# Preamp.net
KiCad netlist of a schematic drawn in Altium Designer
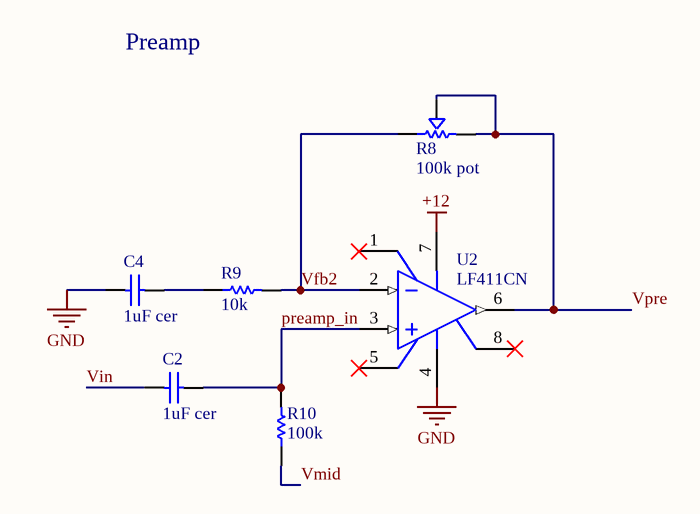
[diagram p0: Preamp.SchDoc]

(export (version "E")
  (design (tool "Eeschema 10.0.6"))
  (components
    (comp (ref "C2")
      (value "1uF cer")
      (footprint "PCB-19304320-1")
      (description "Capacitor; Ceramic; Cap 1.00uF; Tol 10%; Radial; Vol-Rtg 50V")
      (fields (field (name "MANUFACTURER PART NUMBER") "C330C105K5R5TA"))
      (libsource (lib "Octopart library") (part "SYM-bb267075e97664e1-1"))
    )
    (comp (ref "C4")
      (value "1uF cer")
      (footprint "PCB-19304320-1")
      (description "Capacitor; Ceramic; Cap 1.00uF; Tol 10%; Radial; Vol-Rtg 50V")
      (fields (field (name "MANUFACTURER PART NUMBER") "C330C105K5R5TA"))
      (libsource (lib "Octopart library") (part "SYM-bb267075e97664e1-1"))
    )
    (comp (ref "R8")
      (value "100k pot")
      (footprint "PCB-urdemwrt71ubtqm2k8m7-1")
      (description "Res Conductive Plastic POT 50K Ohm 20% 1/4W 1Turn 3.18mm Pin Panel Mount/Through Hole")
      (fields (field (name "MANUFACTURER PART NUMBER") "3310C-001-503L"))
      (libsource (lib "CommunityVault") (part "SYM-1209584-1"))
    )
    (comp (ref "R9")
      (value "10k")
      (footprint "PCB-ufx52wqpb97u1085hkka-1")
      (description "Through Hole Carbon Film Resistor, CFR Series, 10 kohm, 500 mW, - 5%, 350 V, Axial Leaded")
      (libsource (lib "Octopart library") (part "SYM-0abbc281a318d57c-1"))
    )
    (comp (ref "R10")
      (value "100k")
      (footprint "PCB-ufx52wqpb97u1085hkka-1")
      (description "Through Hole Carbon Film Resistor, CFR Series, 10 kohm, 500 mW, - 5%, 350 V, Axial Leaded")
      (libsource (lib "Octopart library") (part "SYM-0abbc281a318d57c-1"))
    )
    (comp (ref "U2")
      (value "LF411CN")
      (footprint "N08E")
      (description "Low Offset, Low Drift JFET Input Operational Amplifier, 8-pin MDIP")
      (libsource (lib "Octopart library") (part "AMP-OPA-LF156-8"))
    )
  )
  (nets
    (net (code "1") (name "+12") (class "Default")
      (node (ref "U2") (pin "7") (pinfunction "V+_7") (pintype "power_in"))
    )
    (net (code "2") (name "/Vfb2") (class "Default")
      (node (ref "R8") (pin "1") (pinfunction "1_1") (pintype "passive"))
      (node (ref "R9") (pin "2") (pinfunction "2_2") (pintype "passive"))
      (node (ref "U2") (pin "2") (pinfunction "IN-_2") (pintype "input"))
    )
    (net (code "3") (name "/Vin") (class "Default")
      (node (ref "C2") (pin "1") (pinfunction "1_1") (pintype "passive"))
    )
    (net (code "4") (name "/Vmid") (class "Default")
      (node (ref "R10") (pin "1") (pinfunction "1_1") (pintype "passive"))
    )
    (net (code "5") (name "/Vpre") (class "Default")
      (node (ref "R8") (pin "2") (pinfunction "2_2") (pintype "passive"))
      (node (ref "R8") (pin "3") (pinfunction "3_3") (pintype "passive"))
      (node (ref "U2") (pin "6") (pinfunction "OUT_6") (pintype "output"))
    )
    (net (code "6") (name "/preamp_in") (class "Default")
      (node (ref "C2") (pin "2") (pinfunction "2_2") (pintype "passive"))
      (node (ref "R10") (pin "2") (pinfunction "2_2") (pintype "passive"))
      (node (ref "U2") (pin "3") (pinfunction "IN+_3") (pintype "input"))
    )
    (net (code "7") (name "GND") (class "Default")
      (node (ref "C4") (pin "1") (pinfunction "1_1") (pintype "passive"))
      (node (ref "U2") (pin "4") (pinfunction "V-_4") (pintype "power_in"))
    )
    (net (code "8") (name "Net-(C4-Pad2)") (class "Default")
      (node (ref "C4") (pin "2") (pinfunction "2_2") (pintype "passive"))
      (node (ref "R9") (pin "1") (pinfunction "1_1") (pintype "passive"))
    )
    (net (code "9") (name "unconnected-(U2-BAL-Pad1)") (class "Default")
      (node (ref "U2") (pin "1") (pinfunction "BAL_1") (pintype "passive+no_connect"))
    )
    (net (code "10") (name "unconnected-(U2-BAL-Pad5)") (class "Default")
      (node (ref "U2") (pin "5") (pinfunction "BAL_5") (pintype "passive+no_connect"))
    )
    (net (code "11") (name "unconnected-(U2-NC-Pad8)") (class "Default")
      (node (ref "U2") (pin "8") (pinfunction "NC_8") (pintype "passive+no_connect"))
    )
  )
)
